# S02-DRIVER.net
KiCad netlist of a schematic drawn in Altium Designer
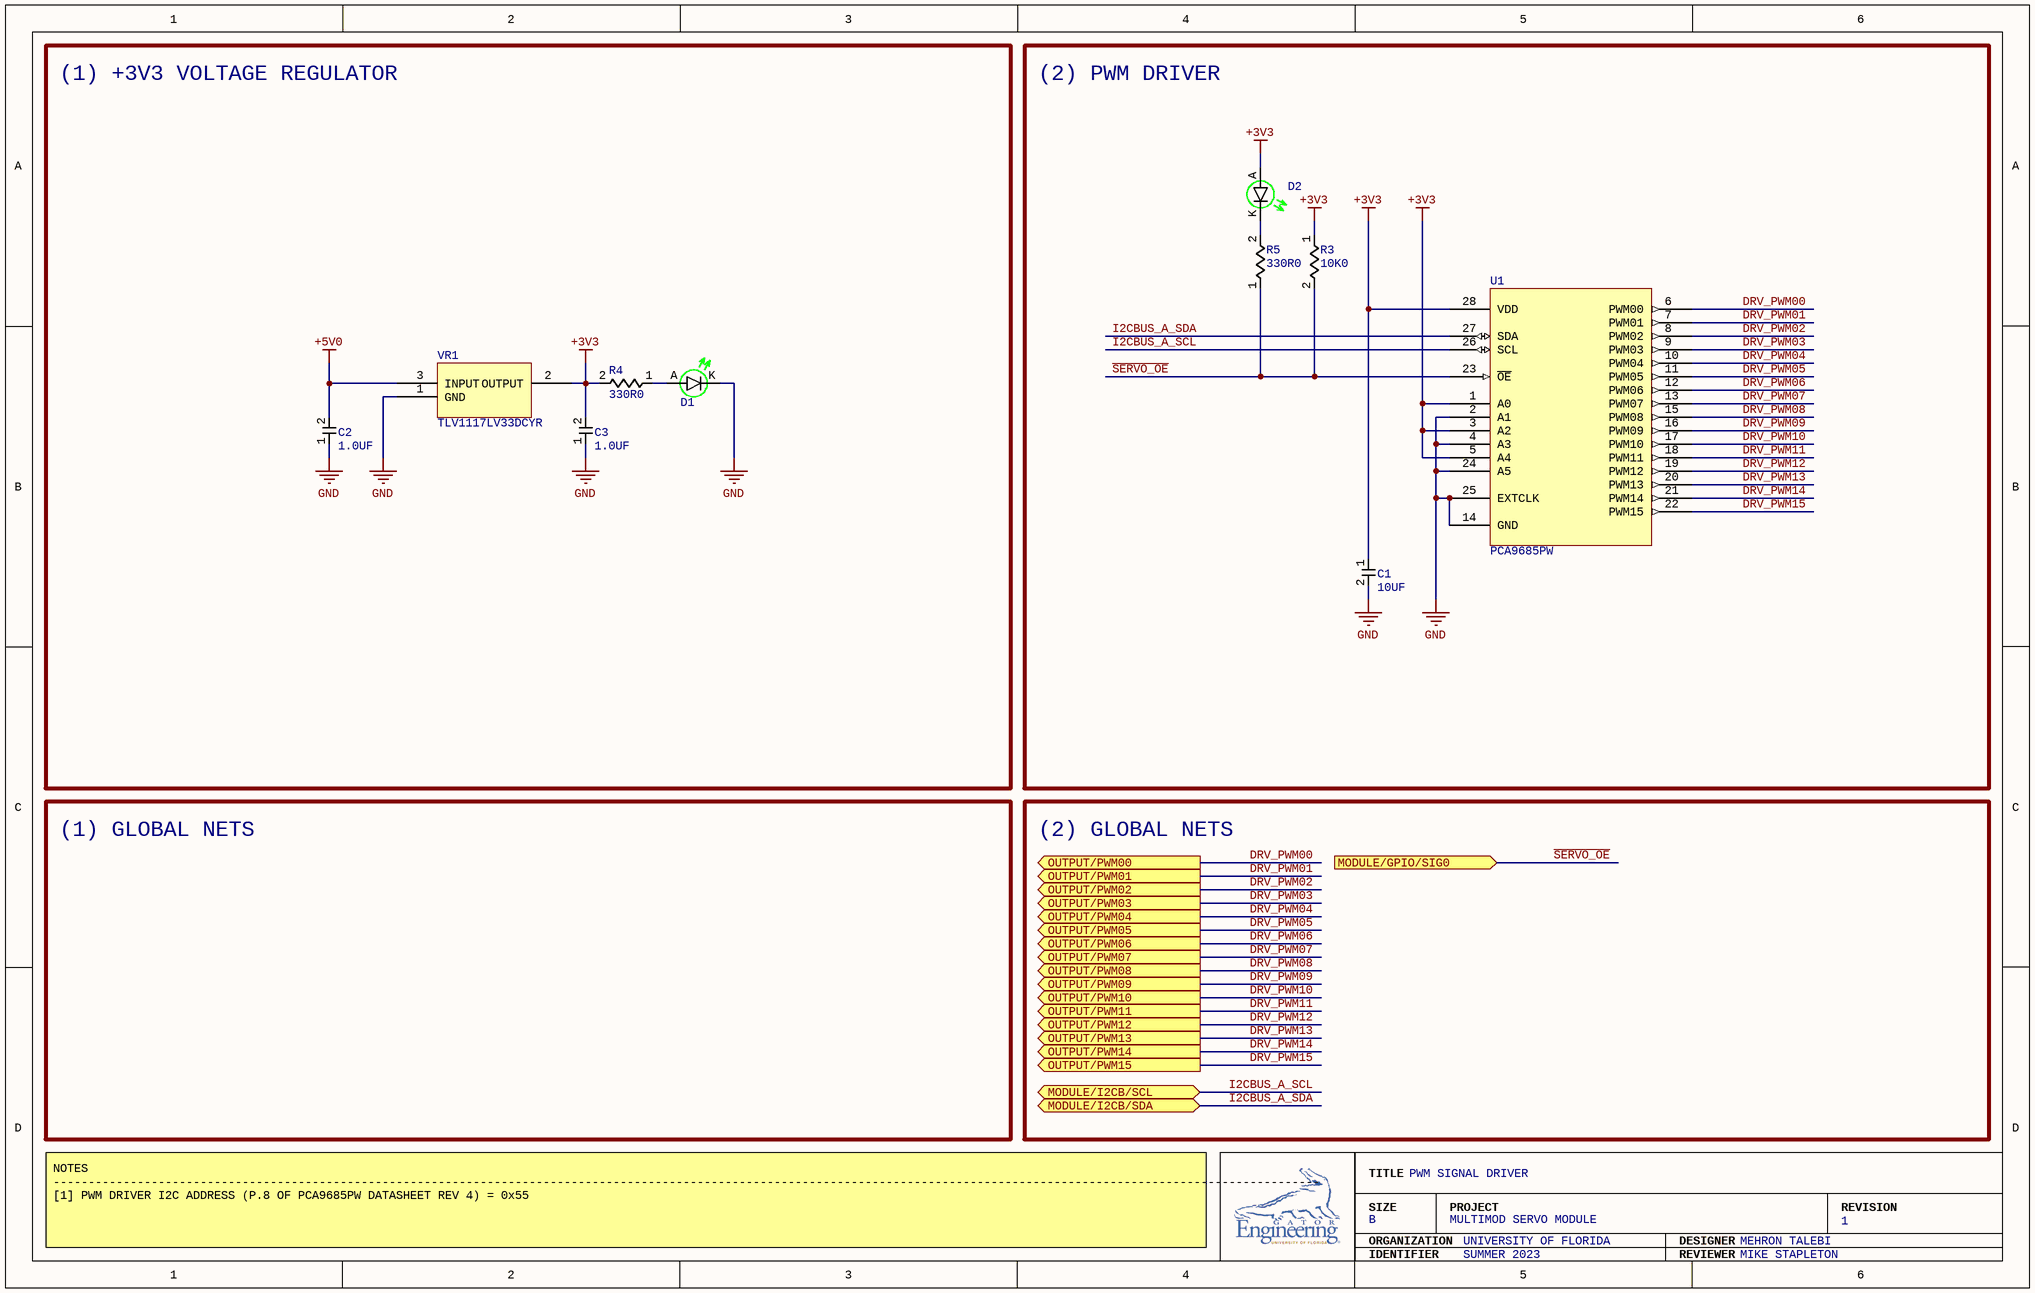
[diagram p0: S02-DRIVER.SchDoc]

(export (version "E")
  (design (tool "Eeschema 10.0.6"))
  (components
    (comp (ref "C1")
      (value "10UF")
      (footprint "CL21B106KPQNFNE")
      (description "CAP CER 10UF 10V X7R 0805")
      (fields (field (name "TOLERANCE") "±10%"))
      (libsource (lib "Master") (part "CL21B106KPQNFNE"))
    )
    (comp (ref "C2")
      (value "1.0UF")
      (footprint "CL21B105KAFNFNE")
      (description "CAP CER 1UF 25V X7R 0805")
      (fields (field (name "TOLERANCE") "±10%"))
      (libsource (lib "Master") (part "CL21B105KAFNFNE"))
    )
    (comp (ref "C3")
      (value "1.0UF")
      (footprint "CL21B105KAFNFNE")
      (description "CAP CER 1UF 25V X7R 0805")
      (fields (field (name "TOLERANCE") "±10%"))
      (libsource (lib "Master") (part "CL21B105KAFNFNE"))
    )
    (comp (ref "D1")
      (value "LTST-C171GKT")
      (footprint "LTST-C171GKT")
      (description "LED GREEN CLEAR CHIP SMD")
      (libsource (lib "Master") (part "LTST-C171GKT"))
    )
    (comp (ref "D2")
      (value "LTST-C171GKT")
      (footprint "LTST-C171GKT")
      (description "LED GREEN CLEAR CHIP SMD")
      (libsource (lib "Master") (part "LTST-C171GKT"))
    )
    (comp (ref "R3")
      (value "10K0")
      (footprint "RC0805FR-0710KL")
      (description "RES 10K OHM 1% 1/8W 0805")
      (fields (field (name "TOLERANCE") "±1%"))
      (libsource (lib "Master") (part "RC0805FR-0710KL"))
    )
    (comp (ref "R4")
      (value "330R0")
      (footprint "RC0805FR-7W330RL")
      (description "RES 330 OHM 1% 1/4W 0805")
      (fields (field (name "TOLERANCE") "±1%"))
      (libsource (lib "Master") (part "RC0805FR-7W330RL"))
    )
    (comp (ref "R5")
      (value "330R0")
      (footprint "RC0805FR-7W330RL")
      (description "RES 330 OHM 1% 1/4W 0805")
      (fields (field (name "TOLERANCE") "±1%"))
      (libsource (lib "Master") (part "RC0805FR-7W330RL"))
    )
    (comp (ref "U1")
      (value "PCA9685PW")
      (footprint "PCA9685PW")
      (description "IC LED DRVR LIN PWM 25MA 28TSSOP")
      (libsource (lib "Master") (part "PCA9685PW"))
    )
    (comp (ref "VR1")
      (value "TLV1117LV33DCYR")
      (footprint "TLV1117LV33DCYR")
      (description "IC REG LINEAR 3.3V 1A SOT223-4")
      (libsource (lib "Master") (part "TLV1117LV33DCYR"))
    )
  )
  (nets
    (net (code "1") (name "+3V3") (class "Default")
      (node (ref "C1") (pin "1") (pinfunction "1_1") (pintype "passive"))
      (node (ref "C3") (pin "2") (pinfunction "2_2") (pintype "passive"))
      (node (ref "D2") (pin "A") (pinfunction "A_A") (pintype "passive"))
      (node (ref "R3") (pin "1") (pinfunction "1_1") (pintype "passive"))
      (node (ref "R4") (pin "2") (pinfunction "2_2") (pintype "passive"))
      (node (ref "U1") (pin "1") (pinfunction "A0_1") (pintype "passive"))
      (node (ref "U1") (pin "28") (pinfunction "VDD_28") (pintype "power_in"))
      (node (ref "U1") (pin "3") (pinfunction "A2_3") (pintype "passive"))
      (node (ref "U1") (pin "5") (pinfunction "A4_5") (pintype "passive"))
      (node (ref "VR1") (pin "2") (pinfunction "OUTPUT_2") (pintype "passive"))
    )
    (net (code "2") (name "+5V0") (class "Default")
      (node (ref "C2") (pin "2") (pinfunction "2_2") (pintype "passive"))
      (node (ref "VR1") (pin "3") (pinfunction "INPUT_3") (pintype "passive"))
    )
    (net (code "3") (name "/DRV_PWM00") (class "Default")
      (node (ref "U1") (pin "6") (pinfunction "PWM00_6") (pintype "output"))
    )
    (net (code "4") (name "/DRV_PWM01") (class "Default")
      (node (ref "U1") (pin "7") (pinfunction "PWM01_7") (pintype "output"))
    )
    (net (code "5") (name "/DRV_PWM02") (class "Default")
      (node (ref "U1") (pin "8") (pinfunction "PWM02_8") (pintype "output"))
    )
    (net (code "6") (name "/DRV_PWM03") (class "Default")
      (node (ref "U1") (pin "9") (pinfunction "PWM03_9") (pintype "output"))
    )
    (net (code "7") (name "/DRV_PWM04") (class "Default")
      (node (ref "U1") (pin "10") (pinfunction "PWM04_10") (pintype "output"))
    )
    (net (code "8") (name "/DRV_PWM05") (class "Default")
      (node (ref "U1") (pin "11") (pinfunction "PWM05_11") (pintype "output"))
    )
    (net (code "9") (name "/DRV_PWM06") (class "Default")
      (node (ref "U1") (pin "12") (pinfunction "PWM06_12") (pintype "output"))
    )
    (net (code "10") (name "/DRV_PWM07") (class "Default")
      (node (ref "U1") (pin "13") (pinfunction "PWM07_13") (pintype "output"))
    )
    (net (code "11") (name "/DRV_PWM08") (class "Default")
      (node (ref "U1") (pin "15") (pinfunction "PWM08_15") (pintype "output"))
    )
    (net (code "12") (name "/DRV_PWM09") (class "Default")
      (node (ref "U1") (pin "16") (pinfunction "PWM09_16") (pintype "output"))
    )
    (net (code "13") (name "/DRV_PWM10") (class "Default")
      (node (ref "U1") (pin "17") (pinfunction "PWM10_17") (pintype "output"))
    )
    (net (code "14") (name "/DRV_PWM11") (class "Default")
      (node (ref "U1") (pin "18") (pinfunction "PWM11_18") (pintype "output"))
    )
    (net (code "15") (name "/DRV_PWM12") (class "Default")
      (node (ref "U1") (pin "19") (pinfunction "PWM12_19") (pintype "output"))
    )
    (net (code "16") (name "/DRV_PWM13") (class "Default")
      (node (ref "U1") (pin "20") (pinfunction "PWM13_20") (pintype "output"))
    )
    (net (code "17") (name "/DRV_PWM14") (class "Default")
      (node (ref "U1") (pin "21") (pinfunction "PWM14_21") (pintype "output"))
    )
    (net (code "18") (name "/DRV_PWM15") (class "Default")
      (node (ref "U1") (pin "22") (pinfunction "PWM15_22") (pintype "output"))
    )
    (net (code "19") (name "/I2CBUS_A_SCL") (class "Default")
      (node (ref "U1") (pin "26") (pinfunction "SCL_26") (pintype "bidirectional"))
    )
    (net (code "20") (name "/I2CBUS_A_SDA") (class "Default")
      (node (ref "U1") (pin "27") (pinfunction "SDA_27") (pintype "bidirectional"))
    )
    (net (code "21") (name "/SERVO_OE") (class "Default")
      (node (ref "R3") (pin "2") (pinfunction "2_2") (pintype "passive"))
      (node (ref "R5") (pin "1") (pinfunction "1_1") (pintype "passive"))
      (node (ref "U1") (pin "23") (pinfunction "OE_23") (pintype "input"))
    )
    (net (code "22") (name "GND") (class "Default")
      (node (ref "C1") (pin "2") (pinfunction "2_2") (pintype "passive"))
      (node (ref "C2") (pin "1") (pinfunction "1_1") (pintype "passive"))
      (node (ref "C3") (pin "1") (pinfunction "1_1") (pintype "passive"))
      (node (ref "D1") (pin "K") (pinfunction "K_K") (pintype "passive"))
      (node (ref "U1") (pin "14") (pinfunction "GND_14") (pintype "power_in"))
      (node (ref "U1") (pin "2") (pinfunction "A1_2") (pintype "passive"))
      (node (ref "U1") (pin "24") (pinfunction "A5_24") (pintype "passive"))
      (node (ref "U1") (pin "25") (pinfunction "EXTCLK_25") (pintype "passive"))
      (node (ref "U1") (pin "4") (pinfunction "A3_4") (pintype "passive"))
      (node (ref "VR1") (pin "1") (pinfunction "GND_1") (pintype "passive"))
    )
    (net (code "23") (name "Net-(D1-PadA)") (class "Default")
      (node (ref "D1") (pin "A") (pinfunction "A_A") (pintype "passive"))
      (node (ref "R4") (pin "1") (pinfunction "1_1") (pintype "passive"))
    )
    (net (code "24") (name "Net-(D2-PadK)") (class "Default")
      (node (ref "D2") (pin "K") (pinfunction "K_K") (pintype "passive"))
      (node (ref "R5") (pin "2") (pinfunction "2_2") (pintype "passive"))
    )
  )
)
